# ESP_Grow_Main_Rev_A_1_Con.net
KiCad netlist of a schematic drawn in Altium Designer
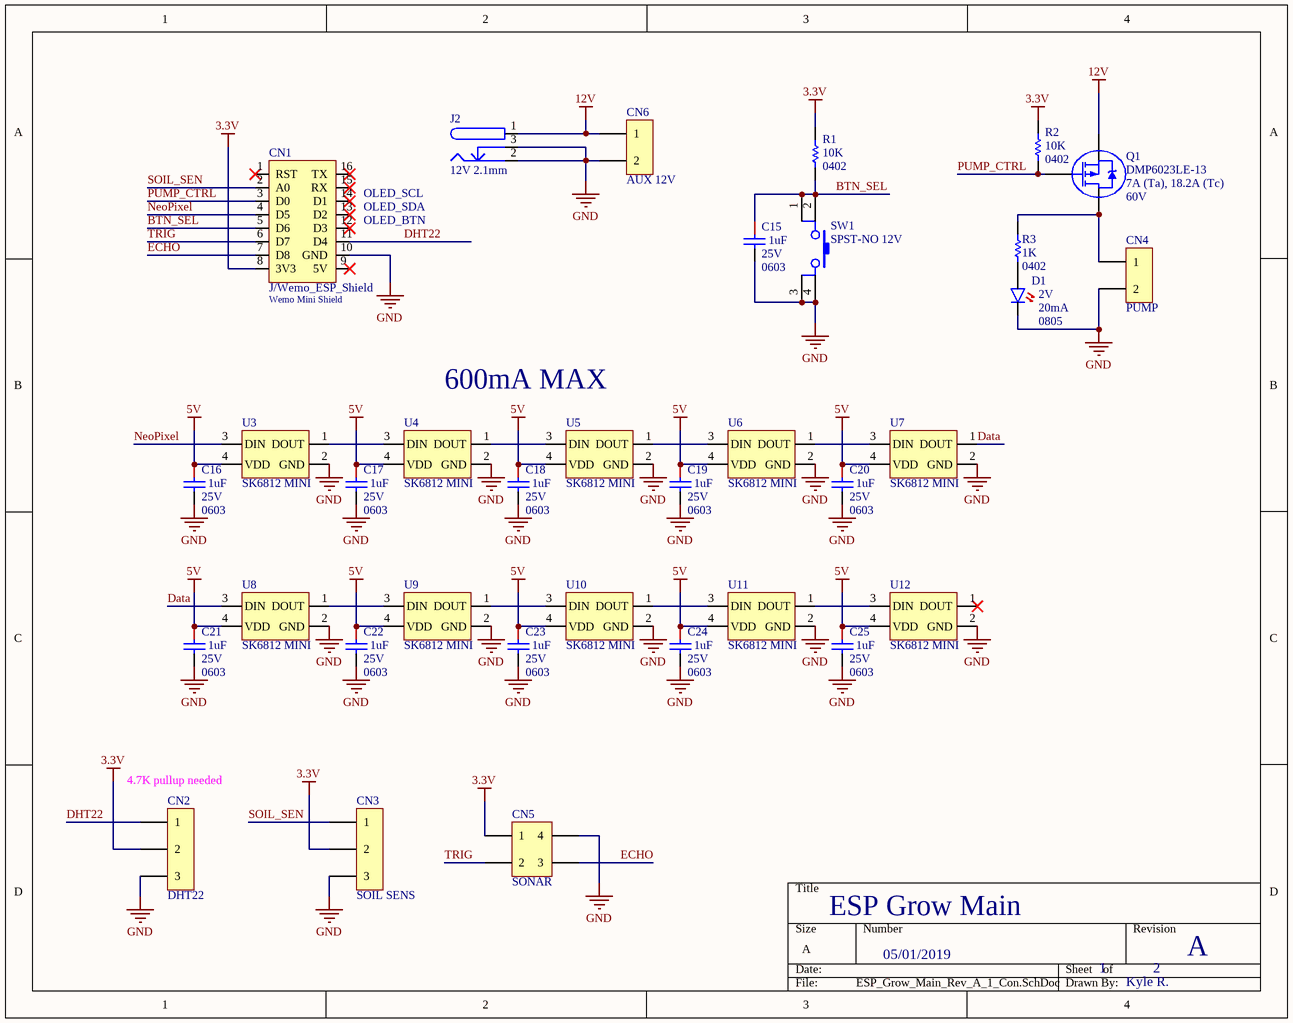
[diagram p0: ESP_Grow_Main_Rev_A_1_Con.SchDoc]

(export (version "E")
  (design (tool "Eeschema 10.0.6"))
  (components
    (comp (ref "C15")
      (value "1uF")
      (footprint "CAPC0603(1608)_N")
      (description "1uF 0603 25V")
      (fields
        (field (name "MANUFACTURER") "TDK Corporation")
        (field (name "MANUFACTURER PART NUMBER") "CGA3E1X7R1E105K080AC")
        (field (name "VOLTAGE - RATED") "25V")
        (field (name "PACKAGE / CASE") "0603")
      )
      (libsource (lib "OLogic-Passive") (part "CAP CER 1UF 25V 10% X7R 0603"))
    )
    (comp (ref "C16")
      (value "1uF")
      (footprint "CAPC0603(1608)_N")
      (description "1uF 0603 25V")
      (fields
        (field (name "MANUFACTURER") "TDK Corporation")
        (field (name "MANUFACTURER PART NUMBER") "CGA3E1X7R1E105K080AC")
        (field (name "VOLTAGE - RATED") "25V")
        (field (name "PACKAGE / CASE") "0603")
      )
      (libsource (lib "OLogic-Passive") (part "CAP CER 1UF 25V 10% X7R 0603"))
    )
    (comp (ref "C17")
      (value "1uF")
      (footprint "CAPC0603(1608)_N")
      (description "1uF 0603 25V")
      (fields
        (field (name "MANUFACTURER") "TDK Corporation")
        (field (name "MANUFACTURER PART NUMBER") "CGA3E1X7R1E105K080AC")
        (field (name "VOLTAGE - RATED") "25V")
        (field (name "PACKAGE / CASE") "0603")
      )
      (libsource (lib "OLogic-Passive") (part "CAP CER 1UF 25V 10% X7R 0603"))
    )
    (comp (ref "C18")
      (value "1uF")
      (footprint "CAPC0603(1608)_N")
      (description "1uF 0603 25V")
      (fields
        (field (name "MANUFACTURER") "TDK Corporation")
        (field (name "MANUFACTURER PART NUMBER") "CGA3E1X7R1E105K080AC")
        (field (name "VOLTAGE - RATED") "25V")
        (field (name "PACKAGE / CASE") "0603")
      )
      (libsource (lib "OLogic-Passive") (part "CAP CER 1UF 25V 10% X7R 0603"))
    )
    (comp (ref "C19")
      (value "1uF")
      (footprint "CAPC0603(1608)_N")
      (description "1uF 0603 25V")
      (fields
        (field (name "MANUFACTURER") "TDK Corporation")
        (field (name "MANUFACTURER PART NUMBER") "CGA3E1X7R1E105K080AC")
        (field (name "VOLTAGE - RATED") "25V")
        (field (name "PACKAGE / CASE") "0603")
      )
      (libsource (lib "OLogic-Passive") (part "CAP CER 1UF 25V 10% X7R 0603"))
    )
    (comp (ref "C20")
      (value "1uF")
      (footprint "CAPC0603(1608)_N")
      (description "1uF 0603 25V")
      (fields
        (field (name "MANUFACTURER") "TDK Corporation")
        (field (name "MANUFACTURER PART NUMBER") "CGA3E1X7R1E105K080AC")
        (field (name "VOLTAGE - RATED") "25V")
        (field (name "PACKAGE / CASE") "0603")
      )
      (libsource (lib "OLogic-Passive") (part "CAP CER 1UF 25V 10% X7R 0603"))
    )
    (comp (ref "C21")
      (value "1uF")
      (footprint "CAPC0603(1608)_N")
      (description "1uF 0603 25V")
      (fields
        (field (name "MANUFACTURER") "TDK Corporation")
        (field (name "MANUFACTURER PART NUMBER") "CGA3E1X7R1E105K080AC")
        (field (name "VOLTAGE - RATED") "25V")
        (field (name "PACKAGE / CASE") "0603")
      )
      (libsource (lib "OLogic-Passive") (part "CAP CER 1UF 25V 10% X7R 0603"))
    )
    (comp (ref "C22")
      (value "1uF")
      (footprint "CAPC0603(1608)_N")
      (description "1uF 0603 25V")
      (fields
        (field (name "MANUFACTURER") "TDK Corporation")
        (field (name "MANUFACTURER PART NUMBER") "CGA3E1X7R1E105K080AC")
        (field (name "VOLTAGE - RATED") "25V")
        (field (name "PACKAGE / CASE") "0603")
      )
      (libsource (lib "OLogic-Passive") (part "CAP CER 1UF 25V 10% X7R 0603"))
    )
    (comp (ref "C23")
      (value "1uF")
      (footprint "CAPC0603(1608)_N")
      (description "1uF 0603 25V")
      (fields
        (field (name "MANUFACTURER") "TDK Corporation")
        (field (name "MANUFACTURER PART NUMBER") "CGA3E1X7R1E105K080AC")
        (field (name "VOLTAGE - RATED") "25V")
        (field (name "PACKAGE / CASE") "0603")
      )
      (libsource (lib "OLogic-Passive") (part "CAP CER 1UF 25V 10% X7R 0603"))
    )
    (comp (ref "C24")
      (value "1uF")
      (footprint "CAPC0603(1608)_N")
      (description "1uF 0603 25V")
      (fields
        (field (name "MANUFACTURER") "TDK Corporation")
        (field (name "MANUFACTURER PART NUMBER") "CGA3E1X7R1E105K080AC")
        (field (name "VOLTAGE - RATED") "25V")
        (field (name "PACKAGE / CASE") "0603")
      )
      (libsource (lib "OLogic-Passive") (part "CAP CER 1UF 25V 10% X7R 0603"))
    )
    (comp (ref "C25")
      (value "1uF")
      (footprint "CAPC0603(1608)_N")
      (description "1uF 0603 25V")
      (fields
        (field (name "MANUFACTURER") "TDK Corporation")
        (field (name "MANUFACTURER PART NUMBER") "CGA3E1X7R1E105K080AC")
        (field (name "VOLTAGE - RATED") "25V")
        (field (name "PACKAGE / CASE") "0603")
      )
      (libsource (lib "OLogic-Passive") (part "CAP CER 1UF 25V 10% X7R 0603"))
    )
    (comp (ref "CN1")
      (value "J/Wemo_ESP_Shield")
      (footprint "Wemos_d1")
      (description "Wemo Mini Shield for ESP-12")
      (fields (field (name "NAME") "Wemo Mini Shield"))
      (libsource (lib "Kyle_Lib_04-20-19") (part "J/Wemo_ESP_Shield"))
    )
    (comp (ref "CN2")
      (value "DHT22")
      (footprint "Molex 1x3 Microfit 90deg")
      (description "Molex Microfit 1x3 90deg Header")
      (fields
        (field (name "MANUFACTURER") "Molex Inc")
        (field (name "MANUFACTURER PART NUMBER") "0436500304")
      )
      (libsource (lib "OLogic-Connectors") (part "MICROFIT 3.0 HDR 90deg 3CKT"))
    )
    (comp (ref "CN3")
      (value "SOIL SENS")
      (footprint "Molex 1x3 Microfit 90deg")
      (description "Molex Microfit 1x3 90deg Header")
      (fields
        (field (name "MANUFACTURER") "Molex Inc")
        (field (name "MANUFACTURER PART NUMBER") "0436500304")
      )
      (libsource (lib "OLogic-Connectors") (part "MICROFIT 3.0 HDR 90deg 3CKT"))
    )
    (comp (ref "CN4")
      (value "PUMP")
      (footprint "Molex 1x2 Microfit 3.0")
      (description "Molex Microfit 1x2 Vert Header")
      (fields
        (field (name "MANUFACTURER") "Molex, LLC")
        (field (name "MANUFACTURER PART NUMBER") "0430450227")
      )
      (libsource (lib "OLogic-Connectors") (part "MICROFIT 3.0 HDR VERT CPI 2CKT"))
    )
    (comp (ref "CN5")
      (value "SONAR")
      (footprint "Molex 2x2 Microfit 90deg")
      (description "Molex Microfit 2x2 90deg Header")
      (fields
        (field (name "MANUFACTURER") "Molex Inc")
        (field (name "MANUFACTURER PART NUMBER") "0430450400")
      )
      (libsource (lib "OLogic-Connectors") (part "MICROFIT 3.0 HDR 90deg 4CKT"))
    )
    (comp (ref "CN6")
      (value "AUX 12V")
      (footprint "Molex 1x2 Microfit 3.0")
      (description "Molex Microfit 1x2 Vert Header")
      (fields
        (field (name "MANUFACTURER") "Molex, LLC")
        (field (name "MANUFACTURER PART NUMBER") "0430450227")
      )
      (libsource (lib "OLogic-Connectors") (part "MICROFIT 3.0 HDR VERT CPI 2CKT"))
    )
    (comp (ref "D1")
      (value "D/LEDR/0805")
      (footprint "D/0805")
      (description "Red 625nm LED Indication - Discrete 2V 0805")
      (fields
        (field (name "DIGIKEY PART") "732-4984-1-ND")
        (field (name "VOLTAGE - FORWARD (VF) (TYP)") "2V")
        (field (name "CURRENT - TEST") "20mA")
        (field (name "PACKAGE / CASE") "0805")
      )
      (libsource (lib "Kyle_Lib_04-20-19") (part "D/LEDR/0805"))
    )
    (comp (ref "J2")
      (value "12V 2.1mm")
      (footprint "CONN_PWR_JACK_2.1x5.5mm")
      (description "2.1 mm barrel jack")
      (fields
        (field (name "MANUFACTURER") "CUI Inc")
        (field (name "MANUFACTURER PART NUMBER") "PJ-002A")
        (field (name "PUBLISHER") "Altium Limited")
      )
      (libsource (lib "OLogic-Connectors") (part "CONN PWR JACK 2.1"))
    )
    (comp (ref "Q1")
      (value "DMP6023LE-13")
      (footprint "SOT-223 - DMP6023LE")
      (description "MOSFET P-CH 60V 7A SOT223")
      (fields
        (field (name "MANUFACTURER") "Diodes Incorporated")
        (field (name "CURRENT - CONTINUOUS DRAIN (ID) @ 25°C") "7A (Ta), 18.2A (Tc)")
        (field (name "DRAIN TO SOURCE VOLTAGE (VDSS)") "60V")
      )
      (libsource (lib "OLogic-Trans-Drivers") (part "DMP6023LE-13"))
    )
    (comp (ref "R1")
      (value "10K")
      (footprint "RESC0402(1005)_N")
      (description "10K 0402")
      (fields
        (field (name "MANUFACTURER") "Samsung Electro-Mechanics")
        (field (name "MANUFACTURER PART NUMBER") "RC1005F103CS")
        (field (name "SUPPLIER DEVICE PACKAGE") "0402")
      )
      (libsource (lib "OLogic-Passive") (part "RES 10K OHM 1% 1/16W 0402"))
    )
    (comp (ref "R2")
      (value "10K")
      (footprint "RESC0402(1005)_N")
      (description "10K 0402")
      (fields
        (field (name "MANUFACTURER") "Samsung Electro-Mechanics")
        (field (name "MANUFACTURER PART NUMBER") "RC1005F103CS")
        (field (name "SUPPLIER DEVICE PACKAGE") "0402")
      )
      (libsource (lib "OLogic-Passive") (part "RES 10K OHM 1% 1/16W 0402"))
    )
    (comp (ref "R3")
      (value "1K")
      (footprint "RESC0402(1005)_L")
      (description "1K 0402")
      (fields
        (field (name "MANUFACTURER") "Yageo")
        (field (name "MANUFACTURER PART NUMBER") "RC0402FR-071KL")
        (field (name "RESISTANCE") "1K")
        (field (name "PACKAGE / CASE") "0402")
      )
      (libsource (lib "OLogic-Passive") (part "RES 1K OHM 1% 1/16W 0402"))
    )
    (comp (ref "SW1")
      (value "SPST-NO 12V")
      (footprint "SW TACT Red 6mm x 6mm")
      (description "SWITCH TACTILE SPST-NO 0.05A 12V")
      (fields
        (field (name "MANUFACTURER") "C&K")
        (field (name "MANUFACTURER PART NUMBER") "PTS645SM43SMTR92 LFS")
      )
      (libsource (lib "OLogic-Switches") (part "PTS645SM43SMTR92 LFS"))
    )
    (comp (ref "U3")
      (value "SK6812 MINI")
      (footprint "SK6812_Mini")
      (description "Serial RGB LED SMT5050")
      (libsource (lib "Kyle_Lib_04-20-19") (part "U/SK6812MINI"))
    )
    (comp (ref "U4")
      (value "SK6812 MINI")
      (footprint "SK6812_Mini")
      (description "Serial RGB LED SMT5050")
      (libsource (lib "Kyle_Lib_04-20-19") (part "U/SK6812MINI"))
    )
    (comp (ref "U5")
      (value "SK6812 MINI")
      (footprint "SK6812_Mini")
      (description "Serial RGB LED SMT5050")
      (libsource (lib "Kyle_Lib_04-20-19") (part "U/SK6812MINI"))
    )
    (comp (ref "U6")
      (value "SK6812 MINI")
      (footprint "SK6812_Mini")
      (description "Serial RGB LED SMT5050")
      (libsource (lib "Kyle_Lib_04-20-19") (part "U/SK6812MINI"))
    )
    (comp (ref "U7")
      (value "SK6812 MINI")
      (footprint "SK6812_Mini")
      (description "Serial RGB LED SMT5050")
      (libsource (lib "Kyle_Lib_04-20-19") (part "U/SK6812MINI"))
    )
    (comp (ref "U8")
      (value "SK6812 MINI")
      (footprint "SK6812_Mini")
      (description "Serial RGB LED SMT5050")
      (libsource (lib "Kyle_Lib_04-20-19") (part "U/SK6812MINI"))
    )
    (comp (ref "U9")
      (value "SK6812 MINI")
      (footprint "SK6812_Mini")
      (description "Serial RGB LED SMT5050")
      (libsource (lib "Kyle_Lib_04-20-19") (part "U/SK6812MINI"))
    )
    (comp (ref "U10")
      (value "SK6812 MINI")
      (footprint "SK6812_Mini")
      (description "Serial RGB LED SMT5050")
      (libsource (lib "Kyle_Lib_04-20-19") (part "U/SK6812MINI"))
    )
    (comp (ref "U11")
      (value "SK6812 MINI")
      (footprint "SK6812_Mini")
      (description "Serial RGB LED SMT5050")
      (libsource (lib "Kyle_Lib_04-20-19") (part "U/SK6812MINI"))
    )
    (comp (ref "U12")
      (value "SK6812 MINI")
      (footprint "SK6812_Mini")
      (description "Serial RGB LED SMT5050")
      (libsource (lib "Kyle_Lib_04-20-19") (part "U/SK6812MINI"))
    )
  )
  (nets
    (net (code "1") (name "/BTN_SEL") (class "Default")
      (node (ref "C15") (pin "1") (pinfunction "1_1") (pintype "passive"))
      (node (ref "CN1") (pin "5") (pinfunction "D6_5") (pintype "power_in"))
      (node (ref "R1") (pin "1") (pinfunction "1_1") (pintype "passive"))
      (node (ref "SW1") (pin "1") (pinfunction "1_1") (pintype "passive"))
      (node (ref "SW1") (pin "2") (pinfunction "2_2") (pintype "passive"))
    )
    (net (code "2") (name "/DHT22") (class "Default")
      (node (ref "CN1") (pin "11") (pinfunction "D4_11") (pintype "power_in"))
      (node (ref "CN2") (pin "1") (pinfunction "1_1") (pintype "passive"))
    )
    (net (code "3") (name "/Data") (class "Default")
      (node (ref "U7") (pin "1") (pinfunction "DOUT_1") (pintype "power_in"))
      (node (ref "U8") (pin "3") (pinfunction "DIN_3") (pintype "power_in"))
    )
    (net (code "4") (name "/ECHO") (class "Default")
      (node (ref "CN1") (pin "7") (pinfunction "D8_7") (pintype "power_in"))
      (node (ref "CN5") (pin "3") (pinfunction "3_3") (pintype "passive"))
    )
    (net (code "5") (name "/NeoPixel") (class "Default")
      (node (ref "CN1") (pin "4") (pinfunction "D5_4") (pintype "power_in"))
      (node (ref "U3") (pin "3") (pinfunction "DIN_3") (pintype "power_in"))
    )
    (net (code "6") (name "/PUMP_CTRL") (class "Default")
      (node (ref "CN1") (pin "3") (pinfunction "D0_3") (pintype "power_in"))
      (node (ref "Q1") (pin "G") (pinfunction "G_G") (pintype "passive"))
      (node (ref "R2") (pin "1") (pinfunction "1_1") (pintype "passive"))
    )
    (net (code "7") (name "/SOIL_SEN") (class "Default")
      (node (ref "CN1") (pin "2") (pinfunction "A0_2") (pintype "power_in"))
      (node (ref "CN3") (pin "1") (pinfunction "1_1") (pintype "passive"))
    )
    (net (code "8") (name "/TRIG") (class "Default")
      (node (ref "CN1") (pin "6") (pinfunction "D7_6") (pintype "power_in"))
      (node (ref "CN5") (pin "2") (pinfunction "2_2") (pintype "passive"))
    )
    (net (code "9") (name "3.3V") (class "Default")
      (node (ref "CN1") (pin "8") (pinfunction "3V3_8") (pintype "power_in"))
      (node (ref "CN2") (pin "2") (pinfunction "2_2") (pintype "passive"))
      (node (ref "CN3") (pin "2") (pinfunction "2_2") (pintype "passive"))
      (node (ref "CN5") (pin "1") (pinfunction "1_1") (pintype "passive"))
      (node (ref "R1") (pin "2") (pinfunction "2_2") (pintype "passive"))
      (node (ref "R2") (pin "2") (pinfunction "2_2") (pintype "passive"))
    )
    (net (code "10") (name "5V") (class "Default")
      (node (ref "C16") (pin "1") (pinfunction "1_1") (pintype "passive"))
      (node (ref "C17") (pin "1") (pinfunction "1_1") (pintype "passive"))
      (node (ref "C18") (pin "1") (pinfunction "1_1") (pintype "passive"))
      (node (ref "C19") (pin "1") (pinfunction "1_1") (pintype "passive"))
      (node (ref "C20") (pin "1") (pinfunction "1_1") (pintype "passive"))
      (node (ref "C21") (pin "1") (pinfunction "1_1") (pintype "passive"))
      (node (ref "C22") (pin "1") (pinfunction "1_1") (pintype "passive"))
      (node (ref "C23") (pin "1") (pinfunction "1_1") (pintype "passive"))
      (node (ref "C24") (pin "1") (pinfunction "1_1") (pintype "passive"))
      (node (ref "C25") (pin "1") (pinfunction "1_1") (pintype "passive"))
      (node (ref "U10") (pin "4") (pinfunction "VDD_4") (pintype "power_in"))
      (node (ref "U11") (pin "4") (pinfunction "VDD_4") (pintype "power_in"))
      (node (ref "U12") (pin "4") (pinfunction "VDD_4") (pintype "power_in"))
      (node (ref "U3") (pin "4") (pinfunction "VDD_4") (pintype "power_in"))
      (node (ref "U4") (pin "4") (pinfunction "VDD_4") (pintype "power_in"))
      (node (ref "U5") (pin "4") (pinfunction "VDD_4") (pintype "power_in"))
      (node (ref "U6") (pin "4") (pinfunction "VDD_4") (pintype "power_in"))
      (node (ref "U7") (pin "4") (pinfunction "VDD_4") (pintype "power_in"))
      (node (ref "U8") (pin "4") (pinfunction "VDD_4") (pintype "power_in"))
      (node (ref "U9") (pin "4") (pinfunction "VDD_4") (pintype "power_in"))
    )
    (net (code "11") (name "12V") (class "Default")
      (node (ref "CN6") (pin "1") (pinfunction "1_1") (pintype "passive"))
      (node (ref "J2") (pin "1") (pinfunction "1_1") (pintype "power_in"))
      (node (ref "Q1") (pin "S") (pinfunction "S_S") (pintype "passive"))
    )
    (net (code "12") (name "GND") (class "Default")
      (node (ref "C15") (pin "2") (pinfunction "2_2") (pintype "passive"))
      (node (ref "C16") (pin "2") (pinfunction "2_2") (pintype "passive"))
      (node (ref "C17") (pin "2") (pinfunction "2_2") (pintype "passive"))
      (node (ref "C18") (pin "2") (pinfunction "2_2") (pintype "passive"))
      (node (ref "C19") (pin "2") (pinfunction "2_2") (pintype "passive"))
      (node (ref "C20") (pin "2") (pinfunction "2_2") (pintype "passive"))
      (node (ref "C21") (pin "2") (pinfunction "2_2") (pintype "passive"))
      (node (ref "C22") (pin "2") (pinfunction "2_2") (pintype "passive"))
      (node (ref "C23") (pin "2") (pinfunction "2_2") (pintype "passive"))
      (node (ref "C24") (pin "2") (pinfunction "2_2") (pintype "passive"))
      (node (ref "C25") (pin "2") (pinfunction "2_2") (pintype "passive"))
      (node (ref "CN1") (pin "10") (pinfunction "GND_10") (pintype "power_in"))
      (node (ref "CN2") (pin "3") (pinfunction "3_3") (pintype "passive"))
      (node (ref "CN3") (pin "3") (pinfunction "3_3") (pintype "passive"))
      (node (ref "CN4") (pin "2") (pinfunction "2_2") (pintype "passive"))
      (node (ref "CN5") (pin "4") (pinfunction "4_4") (pintype "passive"))
      (node (ref "CN6") (pin "2") (pinfunction "2_2") (pintype "passive"))
      (node (ref "D1") (pin "1") (pinfunction "1_1") (pintype "passive"))
      (node (ref "J2") (pin "2") (pinfunction "2_2") (pintype "power_in"))
      (node (ref "J2") (pin "3") (pinfunction "3_3") (pintype "power_in"))
      (node (ref "SW1") (pin "3") (pinfunction "3_3") (pintype "passive"))
      (node (ref "SW1") (pin "4") (pinfunction "4_4") (pintype "passive"))
      (node (ref "U10") (pin "2") (pinfunction "GND_2") (pintype "power_in"))
      (node (ref "U11") (pin "2") (pinfunction "GND_2") (pintype "power_in"))
      (node (ref "U12") (pin "2") (pinfunction "GND_2") (pintype "power_in"))
      (node (ref "U3") (pin "2") (pinfunction "GND_2") (pintype "power_in"))
      (node (ref "U4") (pin "2") (pinfunction "GND_2") (pintype "power_in"))
      (node (ref "U5") (pin "2") (pinfunction "GND_2") (pintype "power_in"))
      (node (ref "U6") (pin "2") (pinfunction "GND_2") (pintype "power_in"))
      (node (ref "U7") (pin "2") (pinfunction "GND_2") (pintype "power_in"))
      (node (ref "U8") (pin "2") (pinfunction "GND_2") (pintype "power_in"))
      (node (ref "U9") (pin "2") (pinfunction "GND_2") (pintype "power_in"))
    )
    (net (code "13") (name "Net-(CN4-Pad1)") (class "Default")
      (node (ref "CN4") (pin "1") (pinfunction "1_1") (pintype "passive"))
      (node (ref "Q1") (pin "D") (pinfunction "D_D") (pintype "passive"))
      (node (ref "R3") (pin "2") (pinfunction "2_2") (pintype "passive"))
    )
    (net (code "14") (name "Net-(D1-Pad2)") (class "Default")
      (node (ref "D1") (pin "2") (pinfunction "2_2") (pintype "passive"))
      (node (ref "R3") (pin "1") (pinfunction "1_1") (pintype "passive"))
    )
    (net (code "15") (name "Net-(U3-DOUT)") (class "Default")
      (node (ref "U3") (pin "1") (pinfunction "DOUT_1") (pintype "power_in"))
      (node (ref "U4") (pin "3") (pinfunction "DIN_3") (pintype "power_in"))
    )
    (net (code "16") (name "Net-(U4-DOUT)") (class "Default")
      (node (ref "U4") (pin "1") (pinfunction "DOUT_1") (pintype "power_in"))
      (node (ref "U5") (pin "3") (pinfunction "DIN_3") (pintype "power_in"))
    )
    (net (code "17") (name "Net-(U5-DOUT)") (class "Default")
      (node (ref "U5") (pin "1") (pinfunction "DOUT_1") (pintype "power_in"))
      (node (ref "U6") (pin "3") (pinfunction "DIN_3") (pintype "power_in"))
    )
    (net (code "18") (name "Net-(U6-DOUT)") (class "Default")
      (node (ref "U6") (pin "1") (pinfunction "DOUT_1") (pintype "power_in"))
      (node (ref "U7") (pin "3") (pinfunction "DIN_3") (pintype "power_in"))
    )
    (net (code "19") (name "Net-(U8-DOUT)") (class "Default")
      (node (ref "U8") (pin "1") (pinfunction "DOUT_1") (pintype "power_in"))
      (node (ref "U9") (pin "3") (pinfunction "DIN_3") (pintype "power_in"))
    )
    (net (code "20") (name "Net-(U10-DIN)") (class "Default")
      (node (ref "U10") (pin "3") (pinfunction "DIN_3") (pintype "power_in"))
      (node (ref "U9") (pin "1") (pinfunction "DOUT_1") (pintype "power_in"))
    )
    (net (code "21") (name "Net-(U10-DOUT)") (class "Default")
      (node (ref "U10") (pin "1") (pinfunction "DOUT_1") (pintype "power_in"))
      (node (ref "U11") (pin "3") (pinfunction "DIN_3") (pintype "power_in"))
    )
    (net (code "22") (name "Net-(U11-DOUT)") (class "Default")
      (node (ref "U11") (pin "1") (pinfunction "DOUT_1") (pintype "power_in"))
      (node (ref "U12") (pin "3") (pinfunction "DIN_3") (pintype "power_in"))
    )
    (net (code "23") (name "unconnected-(CN1-5V-Pad9)") (class "Default")
      (node (ref "CN1") (pin "9") (pinfunction "5V_9") (pintype "power_in+no_connect"))
    )
    (net (code "24") (name "unconnected-(CN1-D1-Pad14)") (class "Default")
      (node (ref "CN1") (pin "14") (pinfunction "D1_14") (pintype "power_in+no_connect"))
    )
    (net (code "25") (name "unconnected-(CN1-D2-Pad13)") (class "Default")
      (node (ref "CN1") (pin "13") (pinfunction "D2_13") (pintype "power_in+no_connect"))
    )
    (net (code "26") (name "unconnected-(CN1-D3-Pad12)") (class "Default")
      (node (ref "CN1") (pin "12") (pinfunction "D3_12") (pintype "power_in+no_connect"))
    )
    (net (code "27") (name "unconnected-(CN1-RST-Pad1)") (class "Default")
      (node (ref "CN1") (pin "1") (pinfunction "RST_1") (pintype "power_in+no_connect"))
    )
    (net (code "28") (name "unconnected-(CN1-RX-Pad15)") (class "Default")
      (node (ref "CN1") (pin "15") (pinfunction "RX_15") (pintype "power_in+no_connect"))
    )
    (net (code "29") (name "unconnected-(CN1-TX-Pad16)") (class "Default")
      (node (ref "CN1") (pin "16") (pinfunction "TX_16") (pintype "power_in+no_connect"))
    )
    (net (code "30") (name "unconnected-(U12-DOUT-Pad1)") (class "Default")
      (node (ref "U12") (pin "1") (pinfunction "DOUT_1") (pintype "power_in+no_connect"))
    )
  )
)
